# Simple_Foc_Power.net
KiCad netlist of a schematic drawn in Altium Designer
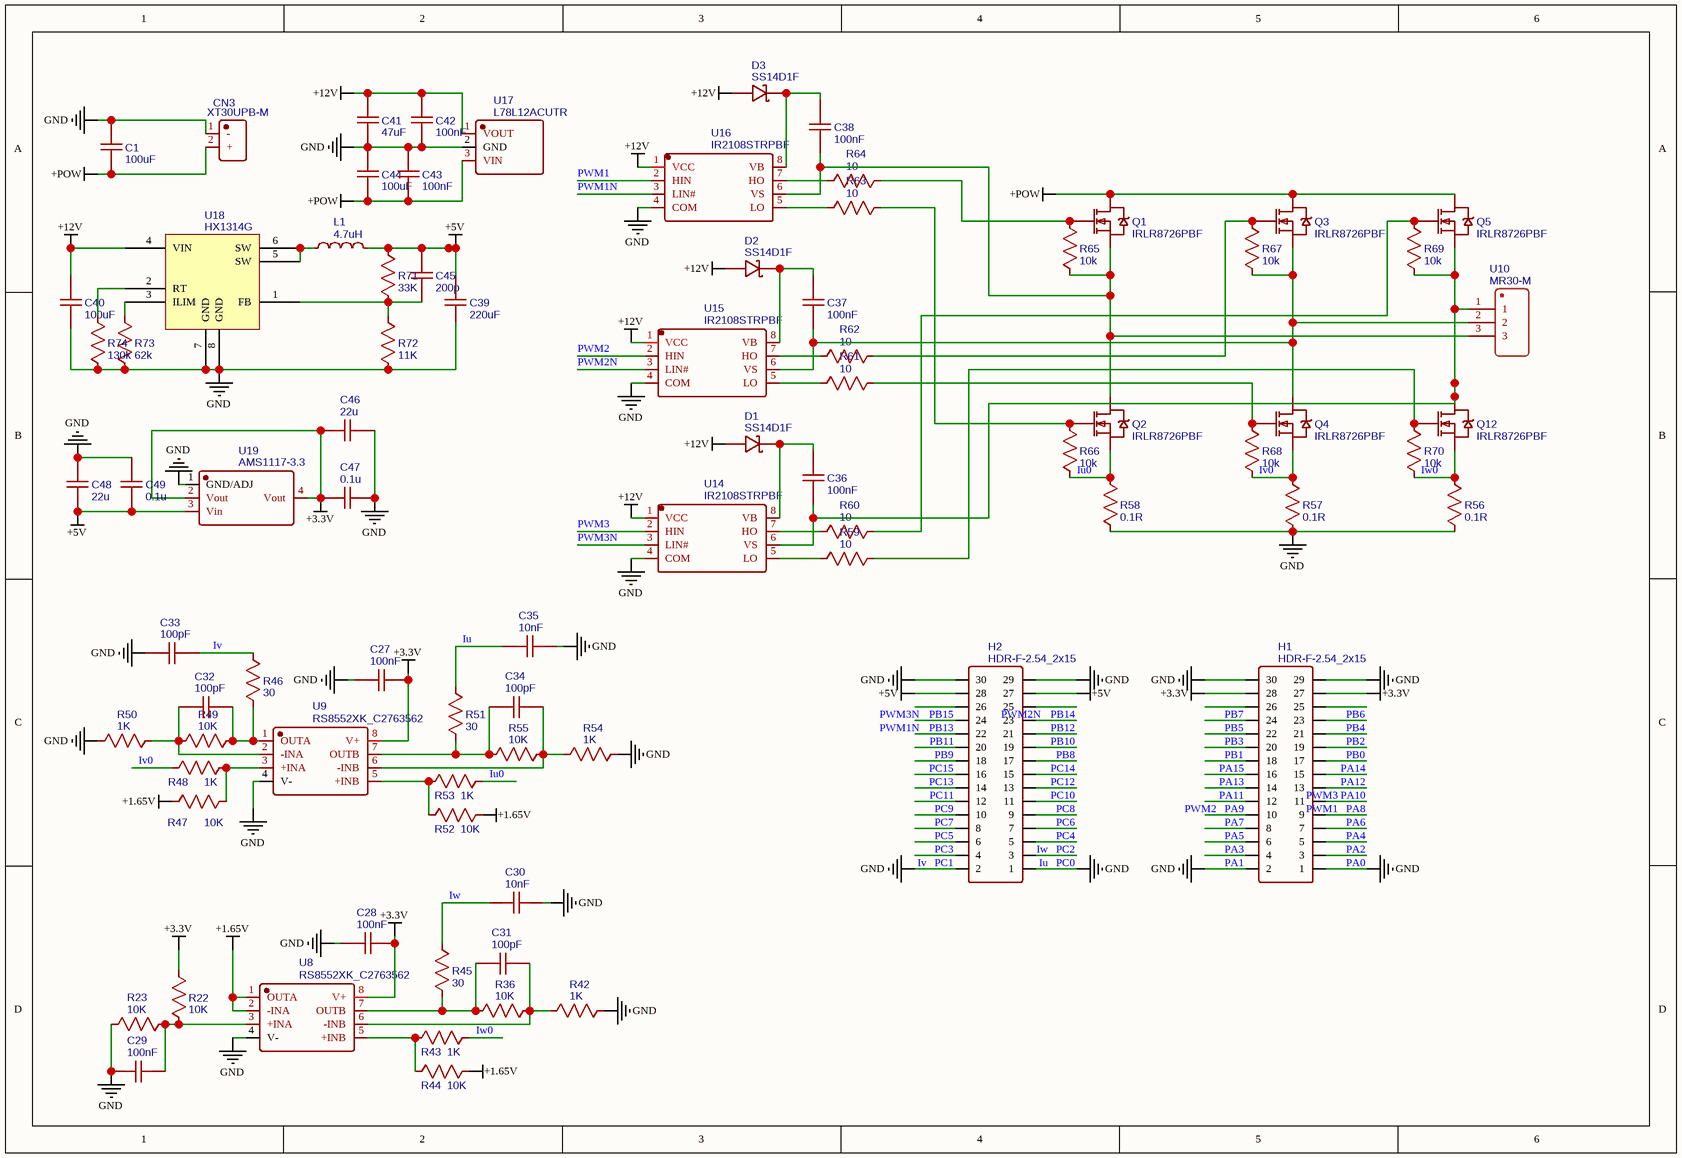
[diagram p0: Simple_Foc_Power.schdoc]

(export (version "E")
  (design (tool "Eeschema 10.0.6"))
  (components
    (comp (ref "C1")
      (value "100uF")
      (fields (field (name "CONTRIBUTOR") "LCEDA_Lib"))
      (libsource (lib "altium-import") (part "root_1_100uF_"))
    )
    (comp (ref "C27")
      (value "100nF")
      (fields (field (name "CONTRIBUTOR") "LCEDA_Lib"))
      (libsource (lib "altium-import") (part "root_0_100nF_"))
    )
    (comp (ref "C28")
      (value "100nF")
      (fields (field (name "CONTRIBUTOR") "LCEDA_Lib"))
      (libsource (lib "altium-import") (part "root_0_100nF_"))
    )
    (comp (ref "C29")
      (value "100nF")
      (fields (field (name "CONTRIBUTOR") "LCEDA_Lib"))
      (libsource (lib "altium-import") (part "root_2_100nF_"))
    )
    (comp (ref "C30")
      (value "10nF")
      (fields (field (name "CONTRIBUTOR") "LCEDA_Lib"))
      (libsource (lib "altium-import") (part "root_2_10nF_"))
    )
    (comp (ref "C31")
      (value "100pF")
      (fields (field (name "CONTRIBUTOR") "LCEDA_Lib"))
      (libsource (lib "altium-import") (part "root_2_100pF_"))
    )
    (comp (ref "C32")
      (value "100pF")
      (fields (field (name "CONTRIBUTOR") "LCEDA_Lib"))
      (libsource (lib "altium-import") (part "root_2_100pF_"))
    )
    (comp (ref "C33")
      (value "100pF")
      (fields (field (name "CONTRIBUTOR") "LCEDA_Lib"))
      (libsource (lib "altium-import") (part "root_2_100pF_"))
    )
    (comp (ref "C34")
      (value "100pF")
      (fields (field (name "CONTRIBUTOR") "LCEDA_Lib"))
      (libsource (lib "altium-import") (part "root_2_100pF_"))
    )
    (comp (ref "C35")
      (value "10nF")
      (fields (field (name "CONTRIBUTOR") "LCEDA_Lib"))
      (libsource (lib "altium-import") (part "root_2_10nF_"))
    )
    (comp (ref "C36")
      (value "100nF")
      (fields (field (name "CONTRIBUTOR") "LCEDA_Lib"))
      (libsource (lib "altium-import") (part "root_1_100nF_"))
    )
    (comp (ref "C37")
      (value "100nF")
      (fields (field (name "CONTRIBUTOR") "LCEDA_Lib"))
      (libsource (lib "altium-import") (part "root_1_100nF_"))
    )
    (comp (ref "C38")
      (value "100nF")
      (fields (field (name "CONTRIBUTOR") "LCEDA_Lib"))
      (libsource (lib "altium-import") (part "root_1_100nF_"))
    )
    (comp (ref "C39")
      (value "220uF")
      (fields (field (name "CONTRIBUTOR") "LCEDA_Lib"))
      (libsource (lib "altium-import") (part "root_1_220uF_"))
    )
    (comp (ref "C40")
      (value "100uF")
      (fields (field (name "CONTRIBUTOR") "LCEDA_Lib"))
      (libsource (lib "altium-import") (part "root_1_100uF_"))
    )
    (comp (ref "C41")
      (value "47uF")
      (fields (field (name "CONTRIBUTOR") "LCEDA_Lib"))
      (libsource (lib "altium-import") (part "root_1_47uF_"))
    )
    (comp (ref "C42")
      (value "100nF")
      (fields (field (name "CONTRIBUTOR") "LCEDA_Lib"))
      (libsource (lib "altium-import") (part "root_1_100nF_"))
    )
    (comp (ref "C43")
      (value "100nF")
      (fields (field (name "CONTRIBUTOR") "LCEDA_Lib"))
      (libsource (lib "altium-import") (part "root_1_100nF_"))
    )
    (comp (ref "C44")
      (value "100uF")
      (fields (field (name "CONTRIBUTOR") "LCEDA_Lib"))
      (libsource (lib "altium-import") (part "root_1_100uF_"))
    )
    (comp (ref "C45")
      (value "200p")
      (fields (field (name "CONTRIBUTOR") "LCEDA_Lib"))
      (libsource (lib "altium-import") (part "root_1_200p_"))
    )
    (comp (ref "C46")
      (value "22u")
      (fields (field (name "CONTRIBUTOR") "LCEDA_Lib"))
      (libsource (lib "altium-import") (part "root_0_22u_"))
    )
    (comp (ref "C47")
      (value "0.1u")
      (fields (field (name "CONTRIBUTOR") "LCEDA_Lib"))
      (libsource (lib "altium-import") (part "root_0_0.1u_"))
    )
    (comp (ref "C48")
      (value "22u")
      (fields (field (name "CONTRIBUTOR") "LCEDA_Lib"))
      (libsource (lib "altium-import") (part "root_1_22u_"))
    )
    (comp (ref "C49")
      (value "0.1u")
      (fields (field (name "CONTRIBUTOR") "LCEDA_Lib"))
      (libsource (lib "altium-import") (part "root_1_0.1u_"))
    )
    (comp (ref "CN3")
      (value "XT30UPB-M")
      (fields (field (name "BOM_SUPPLIER PART") "C428721") (field (name "CONTRIBUTOR") "LCSC"))
      (libsource (lib "altium-import") (part "root_0_XT30UPB-M_"))
    )
    (comp (ref "D1")
      (value "SS14D1F")
      (fields (field (name "BOM_SUPPLIER PART") "C555467") (field (name "CONTRIBUTOR") "LCSC"))
      (libsource (lib "altium-import") (part "root_2_SS14D1F_"))
    )
    (comp (ref "D2")
      (value "SS14D1F")
      (fields (field (name "BOM_SUPPLIER PART") "C555467") (field (name "CONTRIBUTOR") "LCSC"))
      (libsource (lib "altium-import") (part "root_2_SS14D1F_"))
    )
    (comp (ref "D3")
      (value "SS14D1F")
      (fields (field (name "BOM_SUPPLIER PART") "C555467") (field (name "CONTRIBUTOR") "LCSC"))
      (libsource (lib "altium-import") (part "root_2_SS14D1F_"))
    )
    (comp (ref "H1")
      (value "HDR-F-2.54_2x15")
      (fields (field (name "BOM_SUPPLIER PART") "C169818") (field (name "CONTRIBUTOR") "LCEDA_Lib"))
      (libsource (lib "altium-import") (part "root_2_HDR-F-2.54_2x15_"))
    )
    (comp (ref "H2")
      (value "HDR-F-2.54_2x15")
      (fields (field (name "BOM_SUPPLIER PART") "C169818") (field (name "CONTRIBUTOR") "LCEDA_Lib"))
      (libsource (lib "altium-import") (part "root_2_HDR-F-2.54_2x15_"))
    )
    (comp (ref "L1")
      (value "4.7uH")
      (fields (field (name "CONTRIBUTOR") "LCEDA_Lib"))
      (libsource (lib "altium-import") (part "root_0_4.7uH_"))
    )
    (comp (ref "Q1")
      (value "IRLR8726PBF")
      (fields (field (name "BOM_SUPPLIER PART") "C110317"))
      (libsource (lib "altium-import") (part "root_0_IRLR8726PBF_"))
    )
    (comp (ref "Q2")
      (value "IRLR8726PBF")
      (fields (field (name "BOM_SUPPLIER PART") "C110317"))
      (libsource (lib "altium-import") (part "root_0_IRLR8726PBF_"))
    )
    (comp (ref "Q3")
      (value "IRLR8726PBF")
      (fields (field (name "BOM_SUPPLIER PART") "C110317"))
      (libsource (lib "altium-import") (part "root_0_IRLR8726PBF_"))
    )
    (comp (ref "Q4")
      (value "IRLR8726PBF")
      (fields (field (name "BOM_SUPPLIER PART") "C110317"))
      (libsource (lib "altium-import") (part "root_0_IRLR8726PBF_"))
    )
    (comp (ref "Q5")
      (value "IRLR8726PBF")
      (fields (field (name "BOM_SUPPLIER PART") "C110317"))
      (libsource (lib "altium-import") (part "root_0_IRLR8726PBF_"))
    )
    (comp (ref "Q12")
      (value "IRLR8726PBF")
      (fields (field (name "BOM_SUPPLIER PART") "C110317"))
      (libsource (lib "altium-import") (part "root_0_IRLR8726PBF_"))
    )
    (comp (ref "R22")
      (value "10K")
      (fields (field (name "CONTRIBUTOR") "LCEDA_Lib"))
      (libsource (lib "altium-import") (part "root_3_10K_"))
    )
    (comp (ref "R23")
      (value "10K")
      (fields (field (name "CONTRIBUTOR") "LCEDA_Lib"))
      (libsource (lib "altium-import") (part "root_2_10K_"))
    )
    (comp (ref "R36")
      (value "10K")
      (fields (field (name "CONTRIBUTOR") "LCEDA_Lib"))
      (libsource (lib "altium-import") (part "root_0_10K_"))
    )
    (comp (ref "R42")
      (value "1K")
      (fields (field (name "CONTRIBUTOR") "LCEDA_Lib"))
      (libsource (lib "altium-import") (part "root_0_1K_"))
    )
    (comp (ref "R43")
      (value "1K")
      (fields (field (name "CONTRIBUTOR") "LCEDA_Lib"))
      (libsource (lib "altium-import") (part "root_0_1K_"))
    )
    (comp (ref "R44")
      (value "10K")
      (fields (field (name "CONTRIBUTOR") "LCEDA_Lib"))
      (libsource (lib "altium-import") (part "root_0_10K_"))
    )
    (comp (ref "R45")
      (value "30")
      (fields (field (name "CONTRIBUTOR") "LCEDA_Lib"))
      (libsource (lib "altium-import") (part "root_1_30_"))
    )
    (comp (ref "R46")
      (value "30")
      (fields (field (name "CONTRIBUTOR") "LCEDA_Lib"))
      (libsource (lib "altium-import") (part "root_1_30_"))
    )
    (comp (ref "R47")
      (value "10K")
      (fields (field (name "CONTRIBUTOR") "LCEDA_Lib"))
      (libsource (lib "altium-import") (part "root_0_10K_"))
    )
    (comp (ref "R48")
      (value "1K")
      (fields (field (name "CONTRIBUTOR") "LCEDA_Lib"))
      (libsource (lib "altium-import") (part "root_0_1K_"))
    )
    (comp (ref "R49")
      (value "10K")
      (fields (field (name "CONTRIBUTOR") "LCEDA_Lib"))
      (libsource (lib "altium-import") (part "root_0_10K_"))
    )
    (comp (ref "R50")
      (value "1K")
      (fields (field (name "CONTRIBUTOR") "LCEDA_Lib"))
      (libsource (lib "altium-import") (part "root_0_1K_"))
    )
    (comp (ref "R51")
      (value "30")
      (fields (field (name "CONTRIBUTOR") "LCEDA_Lib"))
      (libsource (lib "altium-import") (part "root_1_30_"))
    )
    (comp (ref "R52")
      (value "10K")
      (fields (field (name "CONTRIBUTOR") "LCEDA_Lib"))
      (libsource (lib "altium-import") (part "root_0_10K_"))
    )
    (comp (ref "R53")
      (value "1K")
      (fields (field (name "CONTRIBUTOR") "LCEDA_Lib"))
      (libsource (lib "altium-import") (part "root_0_1K_"))
    )
    (comp (ref "R54")
      (value "1K")
      (fields (field (name "CONTRIBUTOR") "LCEDA_Lib"))
      (libsource (lib "altium-import") (part "root_0_1K_"))
    )
    (comp (ref "R55")
      (value "10K")
      (fields (field (name "CONTRIBUTOR") "LCEDA_Lib"))
      (libsource (lib "altium-import") (part "root_0_10K_"))
    )
    (comp (ref "R56")
      (value "0.1R")
      (fields (field (name "CONTRIBUTOR") "LCEDA_Lib"))
      (libsource (lib "altium-import") (part "root_1_0.1R_"))
    )
    (comp (ref "R57")
      (value "0.1R")
      (fields (field (name "CONTRIBUTOR") "LCEDA_Lib"))
      (libsource (lib "altium-import") (part "root_1_0.1R_"))
    )
    (comp (ref "R58")
      (value "0.1R")
      (fields (field (name "CONTRIBUTOR") "LCEDA_Lib"))
      (libsource (lib "altium-import") (part "root_1_0.1R_"))
    )
    (comp (ref "R59")
      (value "10")
      (fields (field (name "CONTRIBUTOR") "LCEDA_Lib"))
      (libsource (lib "altium-import") (part "root_0_10_"))
    )
    (comp (ref "R60")
      (value "10")
      (fields (field (name "CONTRIBUTOR") "LCEDA_Lib"))
      (libsource (lib "altium-import") (part "root_0_10_"))
    )
    (comp (ref "R61")
      (value "10")
      (fields (field (name "CONTRIBUTOR") "LCEDA_Lib"))
      (libsource (lib "altium-import") (part "root_0_10_"))
    )
    (comp (ref "R62")
      (value "10")
      (fields (field (name "CONTRIBUTOR") "LCEDA_Lib"))
      (libsource (lib "altium-import") (part "root_0_10_"))
    )
    (comp (ref "R63")
      (value "10")
      (fields (field (name "CONTRIBUTOR") "LCEDA_Lib"))
      (libsource (lib "altium-import") (part "root_0_10_"))
    )
    (comp (ref "R64")
      (value "10")
      (fields (field (name "CONTRIBUTOR") "LCEDA_Lib"))
      (libsource (lib "altium-import") (part "root_0_10_"))
    )
    (comp (ref "R65")
      (value "10k")
      (fields (field (name "CONTRIBUTOR") "LCEDA_Lib"))
      (libsource (lib "altium-import") (part "root_1_10k_"))
    )
    (comp (ref "R66")
      (value "10k")
      (fields (field (name "CONTRIBUTOR") "LCEDA_Lib"))
      (libsource (lib "altium-import") (part "root_1_10k_"))
    )
    (comp (ref "R67")
      (value "10k")
      (fields (field (name "CONTRIBUTOR") "LCEDA_Lib"))
      (libsource (lib "altium-import") (part "root_1_10k_"))
    )
    (comp (ref "R68")
      (value "10k")
      (fields (field (name "CONTRIBUTOR") "LCEDA_Lib"))
      (libsource (lib "altium-import") (part "root_1_10k_"))
    )
    (comp (ref "R69")
      (value "10k")
      (fields (field (name "CONTRIBUTOR") "LCEDA_Lib"))
      (libsource (lib "altium-import") (part "root_1_10k_"))
    )
    (comp (ref "R70")
      (value "10k")
      (fields (field (name "CONTRIBUTOR") "LCEDA_Lib"))
      (libsource (lib "altium-import") (part "root_1_10k_"))
    )
    (comp (ref "R71")
      (value "33K")
      (fields (field (name "CONTRIBUTOR") "LCEDA_Lib"))
      (libsource (lib "altium-import") (part "root_1_33K_"))
    )
    (comp (ref "R72")
      (value "11K")
      (fields (field (name "CONTRIBUTOR") "LCEDA_Lib"))
      (libsource (lib "altium-import") (part "root_1_11K_"))
    )
    (comp (ref "R73")
      (value "62k")
      (fields (field (name "CONTRIBUTOR") "LCEDA_Lib"))
      (libsource (lib "altium-import") (part "root_1_62k_"))
    )
    (comp (ref "R74")
      (value "130k")
      (fields (field (name "CONTRIBUTOR") "LCEDA_Lib"))
      (libsource (lib "altium-import") (part "root_1_130k_"))
    )
    (comp (ref "U8")
      (value "RS8552XK_C2763562")
      (fields
        (field (name "BOM_SUPPLIER PART") "C2763562")
        (field (name "BOM_MANUFACTURER PART") "RS8552XK")
        (field (name "CONTRIBUTOR") "LCSC")
      )
      (libsource (lib "altium-import") (part "root_0_RS8552XK_C2763562_"))
    )
    (comp (ref "U9")
      (value "RS8552XK_C2763562")
      (fields
        (field (name "BOM_SUPPLIER PART") "C2763562")
        (field (name "BOM_MANUFACTURER PART") "RS8552XK")
        (field (name "CONTRIBUTOR") "LCSC")
      )
      (libsource (lib "altium-import") (part "root_0_RS8552XK_C2763562_"))
    )
    (comp (ref "U10")
      (value "MR30-M")
      (fields (field (name "CONTRIBUTOR") "杜邦线丶小战士"))
      (libsource (lib "altium-import") (part "root_0_MR30-M_"))
    )
    (comp (ref "U14")
      (value "IR2108STRPBF")
      (fields (field (name "BOM_SUPPLIER PART") "C2964"))
      (libsource (lib "altium-import") (part "root_0_IR2108STRPBF_"))
    )
    (comp (ref "U15")
      (value "IR2108STRPBF")
      (fields (field (name "BOM_SUPPLIER PART") "C2964"))
      (libsource (lib "altium-import") (part "root_0_IR2108STRPBF_"))
    )
    (comp (ref "U16")
      (value "IR2108STRPBF")
      (fields (field (name "BOM_SUPPLIER PART") "C2964"))
      (libsource (lib "altium-import") (part "root_0_IR2108STRPBF_"))
    )
    (comp (ref "U17")
      (value "L78L12ACUTR")
      (fields (field (name "BOM_SUPPLIER PART") "C69601") (field (name "CONTRIBUTOR") "LCSC"))
      (libsource (lib "altium-import") (part "root_0_L78L12ACUTR_"))
    )
    (comp (ref "U18")
      (value "HX1314G")
      (fields (field (name "CONTRIBUTOR") "lzhfz_0591"))
      (libsource (lib "altium-import") (part "root_0_HX1314G_"))
    )
    (comp (ref "U19")
      (value "AMS1117-3.3")
      (fields (field (name "BOM_SUPPLIER PART") "C6186"))
      (libsource (lib "altium-import") (part "root_0_AMS1117-3.3_"))
    )
  )
  (nets
    (net (code "1") (name "+1.65V") (class "Default")
      (node (ref "R44") (pin "2") (pinfunction "2_2") (pintype "passive"))
      (node (ref "R47") (pin "1") (pinfunction "1_1") (pintype "passive"))
      (node (ref "R52") (pin "2") (pinfunction "2_2") (pintype "passive"))
      (node (ref "U8") (pin "1") (pinfunction "OUTA_1") (pintype "passive"))
      (node (ref "U8") (pin "2") (pinfunction "-INA_2") (pintype "passive"))
    )
    (net (code "2") (name "+3.3V") (class "Default")
      (node (ref "C27") (pin "2") (pinfunction "2_2") (pintype "passive"))
      (node (ref "C28") (pin "2") (pinfunction "2_2") (pintype "passive"))
      (node (ref "C46") (pin "1") (pinfunction "1_1") (pintype "passive"))
      (node (ref "C47") (pin "1") (pinfunction "1_1") (pintype "passive"))
      (node (ref "H1") (pin "27") (pinfunction "27_27") (pintype "passive"))
      (node (ref "H1") (pin "28") (pinfunction "28_28") (pintype "passive"))
      (node (ref "R22") (pin "1") (pinfunction "1_1") (pintype "passive"))
      (node (ref "U19") (pin "2") (pinfunction "Vout_2") (pintype "passive"))
      (node (ref "U19") (pin "4") (pinfunction "Vout_4") (pintype "passive"))
      (node (ref "U8") (pin "8") (pinfunction "V+_8") (pintype "passive"))
      (node (ref "U9") (pin "8") (pinfunction "V+_8") (pintype "passive"))
    )
    (net (code "3") (name "+5V") (class "Default")
      (node (ref "C39") (pin "2") (pinfunction "2_2") (pintype "passive"))
      (node (ref "C45") (pin "2") (pinfunction "2_2") (pintype "passive"))
      (node (ref "C48") (pin "1") (pinfunction "1_1") (pintype "passive"))
      (node (ref "C49") (pin "1") (pinfunction "1_1") (pintype "passive"))
      (node (ref "H2") (pin "27") (pinfunction "27_27") (pintype "passive"))
      (node (ref "H2") (pin "28") (pinfunction "28_28") (pintype "passive"))
      (node (ref "L1") (pin "2") (pinfunction "2_2") (pintype "passive"))
      (node (ref "R71") (pin "2") (pinfunction "2_2") (pintype "passive"))
      (node (ref "U19") (pin "3") (pinfunction "Vin_3") (pintype "passive"))
    )
    (net (code "4") (name "+12V") (class "Default")
      (node (ref "C40") (pin "2") (pinfunction "2_2") (pintype "passive"))
      (node (ref "C41") (pin "2") (pinfunction "2_2") (pintype "passive"))
      (node (ref "C42") (pin "2") (pinfunction "2_2") (pintype "passive"))
      (node (ref "D1") (pin "2") (pinfunction "2_2") (pintype "passive"))
      (node (ref "D2") (pin "2") (pinfunction "2_2") (pintype "passive"))
      (node (ref "D3") (pin "2") (pinfunction "2_2") (pintype "passive"))
      (node (ref "U14") (pin "1") (pinfunction "VCC_1") (pintype "passive"))
      (node (ref "U15") (pin "1") (pinfunction "VCC_1") (pintype "passive"))
      (node (ref "U16") (pin "1") (pinfunction "VCC_1") (pintype "passive"))
      (node (ref "U17") (pin "1") (pinfunction "VOUT_1") (pintype "passive"))
      (node (ref "U18") (pin "4") (pinfunction "VIN_4") (pintype "passive"))
    )
    (net (code "5") (name "+POW") (class "Default")
      (node (ref "C1") (pin "1") (pinfunction "1_1") (pintype "passive"))
      (node (ref "C43") (pin "1") (pinfunction "1_1") (pintype "passive"))
      (node (ref "C44") (pin "1") (pinfunction "1_1") (pintype "passive"))
      (node (ref "CN3") (pin "2") (pinfunction "+_2") (pintype "passive"))
      (node (ref "Q1") (pin "2") (pinfunction "D_2") (pintype "passive"))
      (node (ref "Q3") (pin "2") (pinfunction "D_2") (pintype "passive"))
      (node (ref "Q5") (pin "2") (pinfunction "D_2") (pintype "passive"))
      (node (ref "U17") (pin "3") (pinfunction "VIN_3") (pintype "passive"))
    )
    (net (code "6") (name "/Iu") (class "Default")
      (node (ref "C35") (pin "2") (pinfunction "2_2") (pintype "passive"))
      (node (ref "H2") (pin "3") (pinfunction "3_3") (pintype "passive"))
      (node (ref "R51") (pin "2") (pinfunction "2_2") (pintype "passive"))
    )
    (net (code "7") (name "/Iu0") (class "Default")
      (node (ref "Q2") (pin "3") (pinfunction "S_3") (pintype "passive"))
      (node (ref "R53") (pin "2") (pinfunction "2_2") (pintype "passive"))
      (node (ref "R58") (pin "2") (pinfunction "2_2") (pintype "passive"))
      (node (ref "R66") (pin "1") (pinfunction "1_1") (pintype "passive"))
    )
    (net (code "8") (name "/Iv") (class "Default")
      (node (ref "C33") (pin "1") (pinfunction "1_1") (pintype "passive"))
      (node (ref "H2") (pin "4") (pinfunction "4_4") (pintype "passive"))
      (node (ref "R46") (pin "2") (pinfunction "2_2") (pintype "passive"))
    )
    (net (code "9") (name "/Iv0") (class "Default")
      (node (ref "Q4") (pin "3") (pinfunction "S_3") (pintype "passive"))
      (node (ref "R48") (pin "1") (pinfunction "1_1") (pintype "passive"))
      (node (ref "R57") (pin "2") (pinfunction "2_2") (pintype "passive"))
      (node (ref "R68") (pin "1") (pinfunction "1_1") (pintype "passive"))
    )
    (net (code "10") (name "/Iw") (class "Default")
      (node (ref "C30") (pin "2") (pinfunction "2_2") (pintype "passive"))
      (node (ref "H2") (pin "5") (pinfunction "5_5") (pintype "passive"))
      (node (ref "R45") (pin "2") (pinfunction "2_2") (pintype "passive"))
    )
    (net (code "11") (name "/Iw0") (class "Default")
      (node (ref "Q12") (pin "3") (pinfunction "S_3") (pintype "passive"))
      (node (ref "R43") (pin "2") (pinfunction "2_2") (pintype "passive"))
      (node (ref "R56") (pin "2") (pinfunction "2_2") (pintype "passive"))
      (node (ref "R70") (pin "1") (pinfunction "1_1") (pintype "passive"))
    )
    (net (code "12") (name "/PA0") (class "Default")
      (node (ref "H1") (pin "3") (pinfunction "3_3") (pintype "passive"))
    )
    (net (code "13") (name "/PA1") (class "Default")
      (node (ref "H1") (pin "4") (pinfunction "4_4") (pintype "passive"))
    )
    (net (code "14") (name "/PA2") (class "Default")
      (node (ref "H1") (pin "5") (pinfunction "5_5") (pintype "passive"))
    )
    (net (code "15") (name "/PA3") (class "Default")
      (node (ref "H1") (pin "6") (pinfunction "6_6") (pintype "passive"))
    )
    (net (code "16") (name "/PA4") (class "Default")
      (node (ref "H1") (pin "7") (pinfunction "7_7") (pintype "passive"))
    )
    (net (code "17") (name "/PA5") (class "Default")
      (node (ref "H1") (pin "8") (pinfunction "8_8") (pintype "passive"))
    )
    (net (code "18") (name "/PA6") (class "Default")
      (node (ref "H1") (pin "9") (pinfunction "9_9") (pintype "passive"))
    )
    (net (code "19") (name "/PA7") (class "Default")
      (node (ref "H1") (pin "10") (pinfunction "10_10") (pintype "passive"))
    )
    (net (code "20") (name "/PA8") (class "Default")
      (node (ref "H1") (pin "11") (pinfunction "11_11") (pintype "passive"))
      (node (ref "U16") (pin "2") (pinfunction "HIN_2") (pintype "passive"))
    )
    (net (code "21") (name "/PA9") (class "Default")
      (node (ref "H1") (pin "12") (pinfunction "12_12") (pintype "passive"))
      (node (ref "U15") (pin "2") (pinfunction "HIN_2") (pintype "passive"))
    )
    (net (code "22") (name "/PA10") (class "Default")
      (node (ref "H1") (pin "13") (pinfunction "13_13") (pintype "passive"))
      (node (ref "U14") (pin "2") (pinfunction "HIN_2") (pintype "passive"))
    )
    (net (code "23") (name "/PA11") (class "Default")
      (node (ref "H1") (pin "14") (pinfunction "14_14") (pintype "passive"))
    )
    (net (code "24") (name "/PA12") (class "Default")
      (node (ref "H1") (pin "15") (pinfunction "15_15") (pintype "passive"))
    )
    (net (code "25") (name "/PA13") (class "Default")
      (node (ref "H1") (pin "16") (pinfunction "16_16") (pintype "passive"))
    )
    (net (code "26") (name "/PA14") (class "Default")
      (node (ref "H1") (pin "17") (pinfunction "17_17") (pintype "passive"))
    )
    (net (code "27") (name "/PA15") (class "Default")
      (node (ref "H1") (pin "18") (pinfunction "18_18") (pintype "passive"))
    )
    (net (code "28") (name "/PB0") (class "Default")
      (node (ref "H1") (pin "19") (pinfunction "19_19") (pintype "passive"))
    )
    (net (code "29") (name "/PB1") (class "Default")
      (node (ref "H1") (pin "20") (pinfunction "20_20") (pintype "passive"))
    )
    (net (code "30") (name "/PB2") (class "Default")
      (node (ref "H1") (pin "21") (pinfunction "21_21") (pintype "passive"))
    )
    (net (code "31") (name "/PB3") (class "Default")
      (node (ref "H1") (pin "22") (pinfunction "22_22") (pintype "passive"))
    )
    (net (code "32") (name "/PB4") (class "Default")
      (node (ref "H1") (pin "23") (pinfunction "23_23") (pintype "passive"))
    )
    (net (code "33") (name "/PB5") (class "Default")
      (node (ref "H1") (pin "24") (pinfunction "24_24") (pintype "passive"))
    )
    (net (code "34") (name "/PB6") (class "Default")
      (node (ref "H1") (pin "25") (pinfunction "25_25") (pintype "passive"))
    )
    (net (code "35") (name "/PB7") (class "Default")
      (node (ref "H1") (pin "26") (pinfunction "26_26") (pintype "passive"))
    )
    (net (code "36") (name "/PB8") (class "Default")
      (node (ref "H2") (pin "19") (pinfunction "19_19") (pintype "passive"))
    )
    (net (code "37") (name "/PB9") (class "Default")
      (node (ref "H2") (pin "20") (pinfunction "20_20") (pintype "passive"))
    )
    (net (code "38") (name "/PB10") (class "Default")
      (node (ref "H2") (pin "21") (pinfunction "21_21") (pintype "passive"))
    )
    (net (code "39") (name "/PB11") (class "Default")
      (node (ref "H2") (pin "22") (pinfunction "22_22") (pintype "passive"))
    )
    (net (code "40") (name "/PB12") (class "Default")
      (node (ref "H2") (pin "23") (pinfunction "23_23") (pintype "passive"))
    )
    (net (code "41") (name "/PB13") (class "Default")
      (node (ref "H2") (pin "24") (pinfunction "24_24") (pintype "passive"))
      (node (ref "U16") (pin "3") (pinfunction "LIN#_3") (pintype "passive"))
    )
    (net (code "42") (name "/PB14") (class "Default")
      (node (ref "H2") (pin "25") (pinfunction "25_25") (pintype "passive"))
      (node (ref "U15") (pin "3") (pinfunction "LIN#_3") (pintype "passive"))
    )
    (net (code "43") (name "/PB15") (class "Default")
      (node (ref "H2") (pin "26") (pinfunction "26_26") (pintype "passive"))
      (node (ref "U14") (pin "3") (pinfunction "LIN#_3") (pintype "passive"))
    )
    (net (code "44") (name "/PC3") (class "Default")
      (node (ref "H2") (pin "6") (pinfunction "6_6") (pintype "passive"))
    )
    (net (code "45") (name "/PC4") (class "Default")
      (node (ref "H2") (pin "7") (pinfunction "7_7") (pintype "passive"))
    )
    (net (code "46") (name "/PC5") (class "Default")
      (node (ref "H2") (pin "8") (pinfunction "8_8") (pintype "passive"))
    )
    (net (code "47") (name "/PC6") (class "Default")
      (node (ref "H2") (pin "9") (pinfunction "9_9") (pintype "passive"))
    )
    (net (code "48") (name "/PC7") (class "Default")
      (node (ref "H2") (pin "10") (pinfunction "10_10") (pintype "passive"))
    )
    (net (code "49") (name "/PC8") (class "Default")
      (node (ref "H2") (pin "11") (pinfunction "11_11") (pintype "passive"))
    )
    (net (code "50") (name "/PC9") (class "Default")
      (node (ref "H2") (pin "12") (pinfunction "12_12") (pintype "passive"))
    )
    (net (code "51") (name "/PC10") (class "Default")
      (node (ref "H2") (pin "13") (pinfunction "13_13") (pintype "passive"))
    )
    (net (code "52") (name "/PC11") (class "Default")
      (node (ref "H2") (pin "14") (pinfunction "14_14") (pintype "passive"))
    )
    (net (code "53") (name "/PC12") (class "Default")
      (node (ref "H2") (pin "15") (pinfunction "15_15") (pintype "passive"))
    )
    (net (code "54") (name "/PC13") (class "Default")
      (node (ref "H2") (pin "16") (pinfunction "16_16") (pintype "passive"))
    )
    (net (code "55") (name "/PC14") (class "Default")
      (node (ref "H2") (pin "17") (pinfunction "17_17") (pintype "passive"))
    )
    (net (code "56") (name "/PC15") (class "Default")
      (node (ref "H2") (pin "18") (pinfunction "18_18") (pintype "passive"))
    )
    (net (code "57") (name "GND") (class "Default")
      (node (ref "C1") (pin "2") (pinfunction "2_2") (pintype "passive"))
      (node (ref "C27") (pin "1") (pinfunction "1_1") (pintype "passive"))
      (node (ref "C28") (pin "1") (pinfunction "1_1") (pintype "passive"))
      (node (ref "C29") (pin "2") (pinfunction "2_2") (pintype "passive"))
      (node (ref "C30") (pin "1") (pinfunction "1_1") (pintype "passive"))
      (node (ref "C33") (pin "2") (pinfunction "2_2") (pintype "passive"))
      (node (ref "C35") (pin "1") (pinfunction "1_1") (pintype "passive"))
      (node (ref "C39") (pin "1") (pinfunction "1_1") (pintype "passive"))
      (node (ref "C40") (pin "1") (pinfunction "1_1") (pintype "passive"))
      (node (ref "C41") (pin "1") (pinfunction "1_1") (pintype "passive"))
      (node (ref "C42") (pin "1") (pinfunction "1_1") (pintype "passive"))
      (node (ref "C43") (pin "2") (pinfunction "2_2") (pintype "passive"))
      (node (ref "C44") (pin "2") (pinfunction "2_2") (pintype "passive"))
      (node (ref "C46") (pin "2") (pinfunction "2_2") (pintype "passive"))
      (node (ref "C47") (pin "2") (pinfunction "2_2") (pintype "passive"))
      (node (ref "C48") (pin "2") (pinfunction "2_2") (pintype "passive"))
      (node (ref "C49") (pin "2") (pinfunction "2_2") (pintype "passive"))
      (node (ref "CN3") (pin "1") (pinfunction "-_1") (pintype "passive"))
      (node (ref "H1") (pin "1") (pinfunction "1_1") (pintype "passive"))
      (node (ref "H1") (pin "2") (pinfunction "2_2") (pintype "passive"))
      (node (ref "H1") (pin "29") (pinfunction "29_29") (pintype "passive"))
      (node (ref "H1") (pin "30") (pinfunction "30_30") (pintype "passive"))
      (node (ref "H2") (pin "1") (pinfunction "1_1") (pintype "passive"))
      (node (ref "H2") (pin "2") (pinfunction "2_2") (pintype "passive"))
      (node (ref "H2") (pin "29") (pinfunction "29_29") (pintype "passive"))
      (node (ref "H2") (pin "30") (pinfunction "30_30") (pintype "passive"))
      (node (ref "R23") (pin "2") (pinfunction "2_2") (pintype "passive"))
      (node (ref "R42") (pin "2") (pinfunction "2_2") (pintype "passive"))
      (node (ref "R50") (pin "1") (pinfunction "1_1") (pintype "passive"))
      (node (ref "R54") (pin "2") (pinfunction "2_2") (pintype "passive"))
      (node (ref "R56") (pin "1") (pinfunction "1_1") (pintype "passive"))
      (node (ref "R57") (pin "1") (pinfunction "1_1") (pintype "passive"))
      (node (ref "R58") (pin "1") (pinfunction "1_1") (pintype "passive"))
      (node (ref "R72") (pin "1") (pinfunction "1_1") (pintype "passive"))
      (node (ref "R73") (pin "1") (pinfunction "1_1") (pintype "passive"))
      (node (ref "R74") (pin "1") (pinfunction "1_1") (pintype "passive"))
      (node (ref "U14") (pin "4") (pinfunction "COM_4") (pintype "passive"))
      (node (ref "U15") (pin "4") (pinfunction "COM_4") (pintype "passive"))
      (node (ref "U16") (pin "4") (pinfunction "COM_4") (pintype "passive"))
      (node (ref "U17") (pin "2") (pinfunction "GND_2") (pintype "passive"))
      (node (ref "U18") (pin "7") (pinfunction "GND_7") (pintype "passive"))
      (node (ref "U18") (pin "8") (pinfunction "GND_8") (pintype "passive"))
      (node (ref "U19") (pin "1") (pinfunction "GND/ADJ_1") (pintype "passive"))
      (node (ref "U8") (pin "4") (pinfunction "V-_4") (pintype "passive"))
      (node (ref "U9") (pin "4") (pinfunction "V-_4") (pintype "passive"))
    )
    (net (code "58") (name "Net-(L1-Pad1)") (class "Default")
      (node (ref "L1") (pin "1") (pinfunction "1_1") (pintype "passive"))
      (node (ref "U18") (pin "5") (pinfunction "SW_5") (pintype "passive"))
      (node (ref "U18") (pin "6") (pinfunction "SW_6") (pintype "passive"))
    )
    (net (code "59") (name "Net-(Q1-G)") (class "Default")
      (node (ref "Q1") (pin "1") (pinfunction "G_1") (pintype "passive"))
      (node (ref "R64") (pin "2") (pinfunction "2_2") (pintype "passive"))
      (node (ref "R65") (pin "2") (pinfunction "2_2") (pintype "passive"))
    )
    (net (code "60") (name "Net-(Q1-S)") (class "Default")
      (node (ref "C38") (pin "1") (pinfunction "1_1") (pintype "passive"))
      (node (ref "Q1") (pin "3") (pinfunction "S_3") (pintype "passive"))
      (node (ref "Q2") (pin "2") (pinfunction "D_2") (pintype "passive"))
      (node (ref "R65") (pin "1") (pinfunction "1_1") (pintype "passive"))
      (node (ref "U10") (pin "3") (pinfunction "3_3") (pintype "passive"))
      (node (ref "U16") (pin "6") (pinfunction "VS_6") (pintype "passive"))
    )
    (net (code "61") (name "Net-(Q2-G)") (class "Default")
      (node (ref "Q2") (pin "1") (pinfunction "G_1") (pintype "passive"))
      (node (ref "R63") (pin "2") (pinfunction "2_2") (pintype "passive"))
      (node (ref "R66") (pin "2") (pinfunction "2_2") (pintype "passive"))
    )
    (net (code "62") (name "Net-(Q3-G)") (class "Default")
      (node (ref "Q3") (pin "1") (pinfunction "G_1") (pintype "passive"))
      (node (ref "R62") (pin "2") (pinfunction "2_2") (pintype "passive"))
      (node (ref "R67") (pin "2") (pinfunction "2_2") (pintype "passive"))
    )
    (net (code "63") (name "Net-(Q3-S)") (class "Default")
      (node (ref "C37") (pin "1") (pinfunction "1_1") (pintype "passive"))
      (node (ref "Q3") (pin "3") (pinfunction "S_3") (pintype "passive"))
      (node (ref "Q4") (pin "2") (pinfunction "D_2") (pintype "passive"))
      (node (ref "R67") (pin "1") (pinfunction "1_1") (pintype "passive"))
      (node (ref "U10") (pin "2") (pinfunction "2_2") (pintype "passive"))
      (node (ref "U15") (pin "6") (pinfunction "VS_6") (pintype "passive"))
    )
    (net (code "64") (name "Net-(Q4-G)") (class "Default")
      (node (ref "Q4") (pin "1") (pinfunction "G_1") (pintype "passive"))
      (node (ref "R61") (pin "2") (pinfunction "2_2") (pintype "passive"))
      (node (ref "R68") (pin "2") (pinfunction "2_2") (pintype "passive"))
    )
    (net (code "65") (name "Net-(Q5-G)") (class "Default")
      (node (ref "Q5") (pin "1") (pinfunction "G_1") (pintype "passive"))
      (node (ref "R60") (pin "2") (pinfunction "2_2") (pintype "passive"))
      (node (ref "R69") (pin "2") (pinfunction "2_2") (pintype "passive"))
    )
    (net (code "66") (name "Net-(Q12-D)") (class "Default")
      (node (ref "C36") (pin "1") (pinfunction "1_1") (pintype "passive"))
      (node (ref "Q12") (pin "2") (pinfunction "D_2") (pintype "passive"))
      (node (ref "Q5") (pin "3") (pinfunction "S_3") (pintype "passive"))
      (node (ref "R69") (pin "1") (pinfunction "1_1") (pintype "passive"))
      (node (ref "U10") (pin "1") (pinfunction "1_1") (pintype "passive"))
      (node (ref "U14") (pin "6") (pinfunction "VS_6") (pintype "passive"))
    )
    (net (code "67") (name "Net-(Q12-G)") (class "Default")
      (node (ref "Q12") (pin "1") (pinfunction "G_1") (pintype "passive"))
      (node (ref "R59") (pin "2") (pinfunction "2_2") (pintype "passive"))
      (node (ref "R70") (pin "2") (pinfunction "2_2") (pintype "passive"))
    )
    (net (code "68") (name "Net-(U8-+INA)") (class "Default")
      (node (ref "C29") (pin "1") (pinfunction "1_1") (pintype "passive"))
      (node (ref "R22") (pin "2") (pinfunction "2_2") (pintype "passive"))
      (node (ref "R23") (pin "1") (pinfunction "1_1") (pintype "passive"))
      (node (ref "U8") (pin "3") (pinfunction "+INA_3") (pintype "passive"))
    )
    (net (code "69") (name "Net-(U8-+INB)") (class "Default")
      (node (ref "R43") (pin "1") (pinfunction "1_1") (pintype "passive"))
      (node (ref "R44") (pin "1") (pinfunction "1_1") (pintype "passive"))
      (node (ref "U8") (pin "5") (pinfunction "+INB_5") (pintype "passive"))
    )
    (net (code "70") (name "Net-(U8--INB)") (class "Default")
      (node (ref "C31") (pin "1") (pinfunction "1_1") (pintype "passive"))
      (node (ref "R36") (pin "2") (pinfunction "2_2") (pintype "passive"))
      (node (ref "R42") (pin "1") (pinfunction "1_1") (pintype "passive"))
      (node (ref "U8") (pin "6") (pinfunction "-INB_6") (pintype "passive"))
    )
    (net (code "71") (name "Net-(U8-OUTB)") (class "Default")
      (node (ref "C31") (pin "2") (pinfunction "2_2") (pintype "passive"))
      (node (ref "R36") (pin "1") (pinfunction "1_1") (pintype "passive"))
      (node (ref "R45") (pin "1") (pinfunction "1_1") (pintype "passive"))
      (node (ref "U8") (pin "7") (pinfunction "OUTB_7") (pintype "passive"))
    )
    (net (code "72") (name "Net-(U9-+INA)") (class "Default")
      (node (ref "R47") (pin "2") (pinfunction "2_2") (pintype "passive"))
      (node (ref "R48") (pin "2") (pinfunction "2_2") (pintype "passive"))
      (node (ref "U9") (pin "3") (pinfunction "+INA_3") (pintype "passive"))
    )
    (net (code "73") (name "Net-(U9-+INB)") (class "Default")
      (node (ref "R52") (pin "1") (pinfunction "1_1") (pintype "passive"))
      (node (ref "R53") (pin "1") (pinfunction "1_1") (pintype "passive"))
      (node (ref "U9") (pin "5") (pinfunction "+INB_5") (pintype "passive"))
    )
    (net (code "74") (name "Net-(U9--INA)") (class "Default")
      (node (ref "C32") (pin "2") (pinfunction "2_2") (pintype "passive"))
      (node (ref "R49") (pin "1") (pinfunction "1_1") (pintype "passive"))
      (node (ref "R50") (pin "2") (pinfunction "2_2") (pintype "passive"))
      (node (ref "U9") (pin "2") (pinfunction "-INA_2") (pintype "passive"))
    )
    (net (code "75") (name "Net-(U9--INB)") (class "Default")
      (node (ref "C34") (pin "1") (pinfunction "1_1") (pintype "passive"))
      (node (ref "R54") (pin "1") (pinfunction "1_1") (pintype "passive"))
      (node (ref "R55") (pin "2") (pinfunction "2_2") (pintype "passive"))
      (node (ref "U9") (pin "6") (pinfunction "-INB_6") (pintype "passive"))
    )
    (net (code "76") (name "Net-(U9-OUTA)") (class "Default")
      (node (ref "C32") (pin "1") (pinfunction "1_1") (pintype "passive"))
      (node (ref "R46") (pin "1") (pinfunction "1_1") (pintype "passive"))
      (node (ref "R49") (pin "2") (pinfunction "2_2") (pintype "passive"))
      (node (ref "U9") (pin "1") (pinfunction "OUTA_1") (pintype "passive"))
    )
    (net (code "77") (name "Net-(U9-OUTB)") (class "Default")
      (node (ref "C34") (pin "2") (pinfunction "2_2") (pintype "passive"))
      (node (ref "R51") (pin "1") (pinfunction "1_1") (pintype "passive"))
      (node (ref "R55") (pin "1") (pinfunction "1_1") (pintype "passive"))
      (node (ref "U9") (pin "7") (pinfunction "OUTB_7") (pintype "passive"))
    )
    (net (code "78") (name "Net-(U14-HO)") (class "Default")
      (node (ref "R60") (pin "1") (pinfunction "1_1") (pintype "passive"))
      (node (ref "U14") (pin "7") (pinfunction "HO_7") (pintype "passive"))
    )
    (net (code "79") (name "Net-(U14-LO)") (class "Default")
      (node (ref "R59") (pin "1") (pinfunction "1_1") (pintype "passive"))
      (node (ref "U14") (pin "5") (pinfunction "LO_5") (pintype "passive"))
    )
    (net (code "80") (name "Net-(U14-VB)") (class "Default")
      (node (ref "C36") (pin "2") (pinfunction "2_2") (pintype "passive"))
      (node (ref "D1") (pin "1") (pinfunction "1_1") (pintype "passive"))
      (node (ref "U14") (pin "8") (pinfunction "VB_8") (pintype "passive"))
    )
    (net (code "81") (name "Net-(U15-HO)") (class "Default")
      (node (ref "R62") (pin "1") (pinfunction "1_1") (pintype "passive"))
      (node (ref "U15") (pin "7") (pinfunction "HO_7") (pintype "passive"))
    )
    (net (code "82") (name "Net-(U15-LO)") (class "Default")
      (node (ref "R61") (pin "1") (pinfunction "1_1") (pintype "passive"))
      (node (ref "U15") (pin "5") (pinfunction "LO_5") (pintype "passive"))
    )
    (net (code "83") (name "Net-(U15-VB)") (class "Default")
      (node (ref "C37") (pin "2") (pinfunction "2_2") (pintype "passive"))
      (node (ref "D2") (pin "1") (pinfunction "1_1") (pintype "passive"))
      (node (ref "U15") (pin "8") (pinfunction "VB_8") (pintype "passive"))
    )
    (net (code "84") (name "Net-(U16-HO)") (class "Default")
      (node (ref "R64") (pin "1") (pinfunction "1_1") (pintype "passive"))
      (node (ref "U16") (pin "7") (pinfunction "HO_7") (pintype "passive"))
    )
    (net (code "85") (name "Net-(U16-LO)") (class "Default")
      (node (ref "R63") (pin "1") (pinfunction "1_1") (pintype "passive"))
      (node (ref "U16") (pin "5") (pinfunction "LO_5") (pintype "passive"))
    )
    (net (code "86") (name "Net-(U16-VB)") (class "Default")
      (node (ref "C38") (pin "2") (pinfunction "2_2") (pintype "passive"))
      (node (ref "D3") (pin "1") (pinfunction "1_1") (pintype "passive"))
      (node (ref "U16") (pin "8") (pinfunction "VB_8") (pintype "passive"))
    )
    (net (code "87") (name "Net-(U18-FB)") (class "Default")
      (node (ref "C45") (pin "1") (pinfunction "1_1") (pintype "passive"))
      (node (ref "R71") (pin "1") (pinfunction "1_1") (pintype "passive"))
      (node (ref "R72") (pin "2") (pinfunction "2_2") (pintype "passive"))
      (node (ref "U18") (pin "1") (pinfunction "FB_1") (pintype "passive"))
    )
    (net (code "88") (name "Net-(U18-ILIM)") (class "Default")
      (node (ref "R73") (pin "2") (pinfunction "2_2") (pintype "passive"))
      (node (ref "U18") (pin "3") (pinfunction "ILIM_3") (pintype "passive"))
    )
    (net (code "89") (name "Net-(U18-RT)") (class "Default")
      (node (ref "R74") (pin "2") (pinfunction "2_2") (pintype "passive"))
      (node (ref "U18") (pin "2") (pinfunction "RT_2") (pintype "passive"))
    )
  )
)
